# Reader_Schematic.net
KiCad netlist of a schematic drawn in Altium Designer
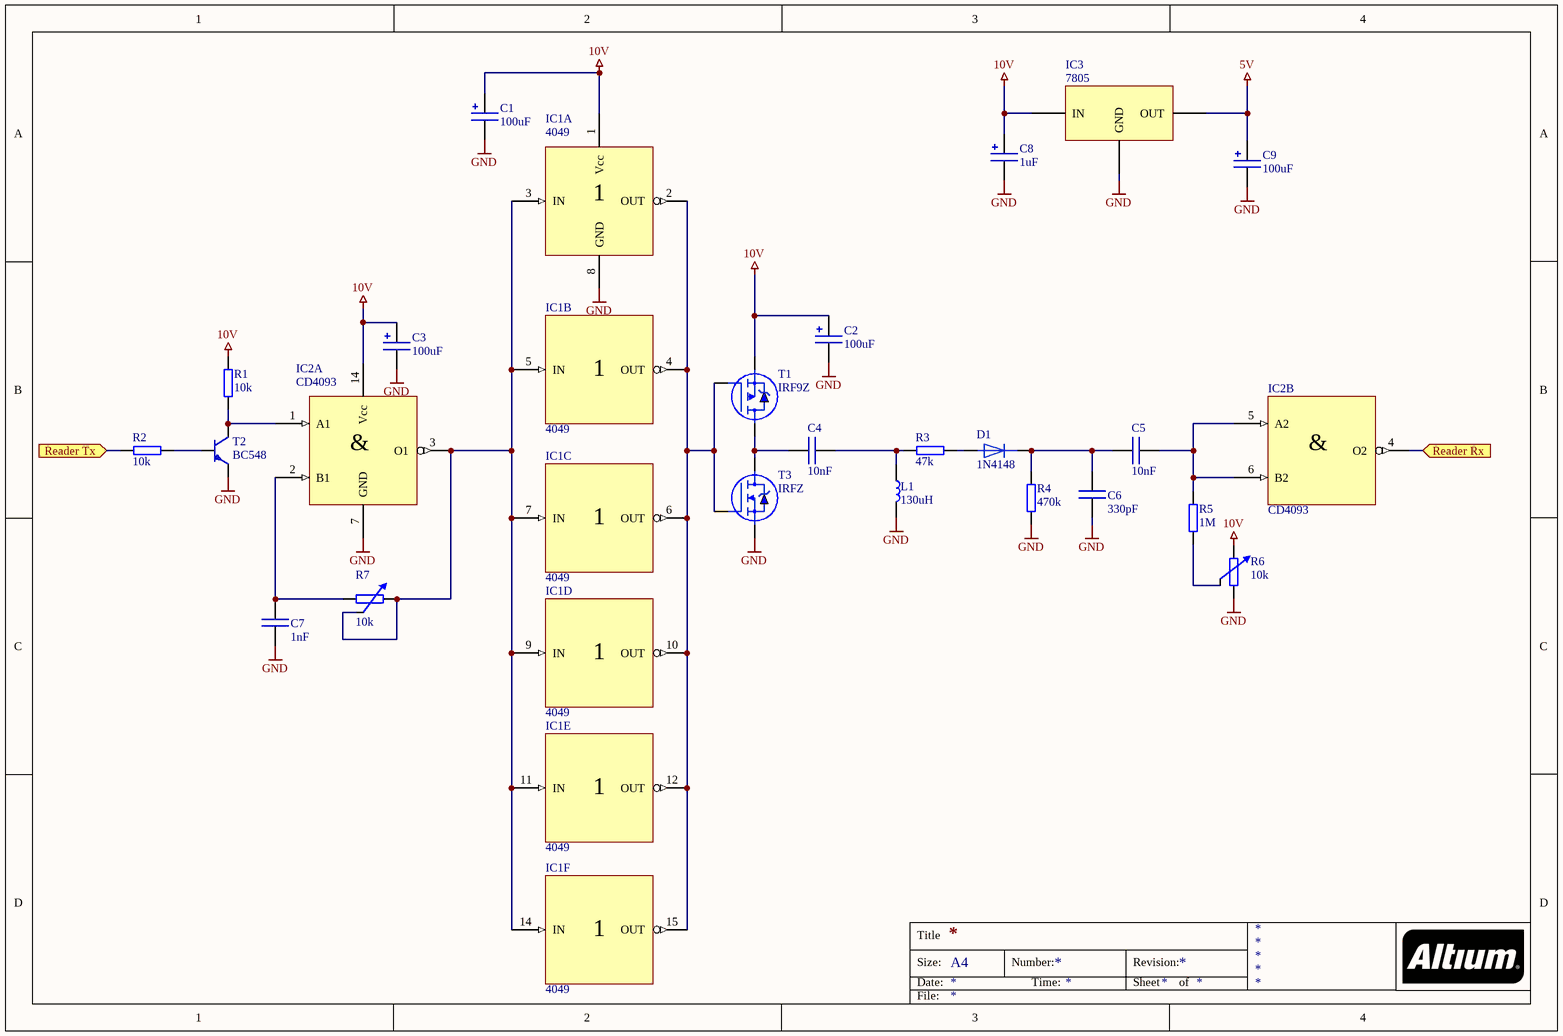
[diagram p0: Reader_Schematic.SchDoc]

(export (version "E")
  (design (tool "Eeschema 10.0.6"))
  (components
    (comp (ref "C1") (value "100uF") (footprint "ELKO_10_5.0") (libsource (lib "Staudi_Lib") (part "Elko")))
    (comp (ref "C2") (value "100uF") (footprint "ELKO_10_5.0") (libsource (lib "Staudi_Lib") (part "Elko")))
    (comp (ref "C3") (value "100uF") (footprint "ELKO_10_5.0") (libsource (lib "Staudi_Lib") (part "Elko")))
    (comp (ref "C4") (value "10nF") (footprint "0805") (libsource (lib "Staudi_Lib") (part "Cap")))
    (comp (ref "C5") (value "10nF") (footprint "0805") (libsource (lib "Staudi_Lib") (part "Cap")))
    (comp (ref "C6") (value "330pF") (footprint "0805") (libsource (lib "Staudi_Lib") (part "Cap")))
    (comp (ref "C7") (value "1nF") (footprint "0805") (libsource (lib "Staudi_Lib") (part "Cap")))
    (comp (ref "C8") (value "1uF") (footprint "ELKO_10_5.0") (libsource (lib "Staudi_Lib") (part "Elko")))
    (comp (ref "C9") (value "100uF") (footprint "ELKO_10_5.0") (libsource (lib "Staudi_Lib") (part "Elko")))
    (comp (ref "D1") (value "1N4148") (libsource (lib "Staudi_Lib") (part "Diode")))
    (comp (ref "IC1")
      (value "4049")
      (description "Hex Inverter")
      (libsource (lib "Staudi_Lib") (part "4049"))
    )
    (comp (ref "IC2")
      (value "CD4093")
      (description "Quad NAND with Schmitt Output")
      (libsource (lib "Staudi_Lib") (part "4093"))
    )
    (comp (ref "IC3")
      (value "7805")
      (description "5V Voltage regulator")
      (libsource (lib "Staudi_Lib") (part "7805"))
    )
    (comp (ref "L1")
      (value "130uH")
      (description "Inductor")
      (libsource (lib "Staudi_Lib") (part "Inductor"))
    )
    (comp (ref "R1") (value "10k") (footprint "Axial-04") (libsource (lib "Staudi_Lib") (part "Res")))
    (comp (ref "R2") (value "10k") (footprint "Axial-04") (libsource (lib "Staudi_Lib") (part "Res")))
    (comp (ref "R3") (value "47k") (footprint "Axial-04") (libsource (lib "Staudi_Lib") (part "Res")))
    (comp (ref "R4") (value "470k") (footprint "Axial-04") (libsource (lib "Staudi_Lib") (part "Res")))
    (comp (ref "R5") (value "1M") (footprint "Axial-04") (libsource (lib "Staudi_Lib") (part "Res")))
    (comp (ref "R6") (value "10k") (libsource (lib "Staudi_Lib") (part "Potentiometer")))
    (comp (ref "R7") (value "10k") (libsource (lib "Staudi_Lib") (part "Potentiometer")))
    (comp (ref "T1")
      (value "IRF9Z")
      (footprint "NDS0610")
      (libsource (lib "Staudi_Lib") (part "MOSFET P-Channel"))
    )
    (comp (ref "T2") (value "BC548") (footprint "2SC3324") (libsource (lib "Staudi_Lib") (part "NPN")))
    (comp (ref "T3")
      (value "IRFZ")
      (footprint "SOT-23")
      (libsource (lib "Staudi_Lib") (part "MOSFET N-Channel"))
    )
  )
  (nets
    (net (code "1") (name "/Reader Rx") (class "Default")
      (node (ref "IC2") (pin "4") (pinfunction "O2_4") (pintype "output"))
    )
    (net (code "2") (name "/Reader Tx") (class "Default")
      (node (ref "R2") (pin "1") (pinfunction "1_1") (pintype "passive"))
    )
    (net (code "3") (name "5V") (class "Default")
      (node (ref "C9") (pin "1") (pinfunction "1_1") (pintype "passive"))
      (node (ref "IC3") (pin "2") (pinfunction "OUT_2") (pintype "passive"))
    )
    (net (code "4") (name "10V") (class "Default")
      (node (ref "C1") (pin "1") (pinfunction "1_1") (pintype "passive"))
      (node (ref "C2") (pin "1") (pinfunction "1_1") (pintype "passive"))
      (node (ref "C3") (pin "1") (pinfunction "1_1") (pintype "passive"))
      (node (ref "C8") (pin "1") (pinfunction "1_1") (pintype "passive"))
      (node (ref "IC1") (pin "1") (pinfunction "Vcc_1") (pintype "passive"))
      (node (ref "IC2") (pin "14") (pinfunction "Vcc_14") (pintype "passive"))
      (node (ref "IC3") (pin "1") (pinfunction "IN_1") (pintype "passive"))
      (node (ref "R1") (pin "2") (pinfunction "2_2") (pintype "passive"))
      (node (ref "R6") (pin "2") (pinfunction "2_2") (pintype "passive"))
      (node (ref "T1") (pin "2") (pinfunction "Source_2") (pintype "passive"))
    )
    (net (code "5") (name "GND") (class "Default")
      (node (ref "C1") (pin "2") (pinfunction "2_2") (pintype "passive"))
      (node (ref "C2") (pin "2") (pinfunction "2_2") (pintype "passive"))
      (node (ref "C3") (pin "2") (pinfunction "2_2") (pintype "passive"))
      (node (ref "C6") (pin "1") (pinfunction "1_1") (pintype "passive"))
      (node (ref "C7") (pin "1") (pinfunction "1_1") (pintype "passive"))
      (node (ref "C8") (pin "2") (pinfunction "2_2") (pintype "passive"))
      (node (ref "C9") (pin "2") (pinfunction "2_2") (pintype "passive"))
      (node (ref "IC1") (pin "8") (pinfunction "GND_8") (pintype "passive"))
      (node (ref "IC2") (pin "7") (pinfunction "GND_7") (pintype "passive"))
      (node (ref "IC3") (pin "3") (pinfunction "GND_3") (pintype "passive"))
      (node (ref "L1") (pin "1") (pinfunction "1_1") (pintype "passive"))
      (node (ref "R4") (pin "1") (pinfunction "1_1") (pintype "passive"))
      (node (ref "R6") (pin "1") (pinfunction "1_1") (pintype "passive"))
      (node (ref "T2") (pin "2") (pinfunction "Emitter_2") (pintype "passive"))
      (node (ref "T3") (pin "3") (pinfunction "Source_3") (pintype "passive"))
    )
    (net (code "6") (name "Net-(C4-Pad2)") (class "Default")
      (node (ref "C4") (pin "2") (pinfunction "2_2") (pintype "passive"))
      (node (ref "L1") (pin "2") (pinfunction "2_2") (pintype "passive"))
      (node (ref "R3") (pin "1") (pinfunction "1_1") (pintype "passive"))
    )
    (net (code "7") (name "Net-(D1-Anode)") (class "Default")
      (node (ref "D1") (pin "1") (pinfunction "Anode_1") (pintype "passive"))
      (node (ref "R3") (pin "2") (pinfunction "2_2") (pintype "passive"))
    )
    (net (code "8") (name "Net-(D1-Kathode)") (class "Default")
      (node (ref "C5") (pin "1") (pinfunction "1_1") (pintype "passive"))
      (node (ref "C6") (pin "2") (pinfunction "2_2") (pintype "passive"))
      (node (ref "D1") (pin "2") (pinfunction "Kathode_2") (pintype "passive"))
      (node (ref "R4") (pin "2") (pinfunction "2_2") (pintype "passive"))
    )
    (net (code "9") (name "Net-(IC1A-IN)") (class "Default")
      (node (ref "IC1") (pin "11") (pinfunction "IN_11") (pintype "input"))
      (node (ref "IC1") (pin "14") (pinfunction "IN_14") (pintype "input"))
      (node (ref "IC1") (pin "3") (pinfunction "IN_3") (pintype "input"))
      (node (ref "IC1") (pin "5") (pinfunction "IN_5") (pintype "input"))
      (node (ref "IC1") (pin "7") (pinfunction "IN_7") (pintype "input"))
      (node (ref "IC1") (pin "9") (pinfunction "IN_9") (pintype "input"))
      (node (ref "IC2") (pin "3") (pinfunction "O1_3") (pintype "output"))
      (node (ref "R7") (pin "2") (pinfunction "2_2") (pintype "passive"))
      (node (ref "R7") (pin "3") (pinfunction "3_3") (pintype "passive"))
    )
    (net (code "10") (name "Net-(IC1A-OUT)") (class "Default")
      (node (ref "IC1") (pin "10") (pinfunction "OUT_10") (pintype "output"))
      (node (ref "IC1") (pin "12") (pinfunction "OUT_12") (pintype "output"))
      (node (ref "IC1") (pin "15") (pinfunction "OUT_15") (pintype "output"))
      (node (ref "IC1") (pin "2") (pinfunction "OUT_2") (pintype "output"))
      (node (ref "IC1") (pin "4") (pinfunction "OUT_4") (pintype "output"))
      (node (ref "IC1") (pin "6") (pinfunction "OUT_6") (pintype "output"))
      (node (ref "T1") (pin "1") (pinfunction "Gate_1") (pintype "passive"))
      (node (ref "T3") (pin "1") (pinfunction "Gate_1") (pintype "passive"))
    )
    (net (code "11") (name "Net-(IC2A-A1)") (class "Default")
      (node (ref "IC2") (pin "1") (pinfunction "A1_1") (pintype "input"))
      (node (ref "R1") (pin "1") (pinfunction "1_1") (pintype "passive"))
      (node (ref "T2") (pin "3") (pinfunction "Collector_3") (pintype "passive"))
    )
    (net (code "12") (name "Net-(IC2A-B1)") (class "Default")
      (node (ref "C7") (pin "2") (pinfunction "2_2") (pintype "passive"))
      (node (ref "IC2") (pin "2") (pinfunction "B1_2") (pintype "input"))
      (node (ref "R7") (pin "1") (pinfunction "1_1") (pintype "passive"))
    )
    (net (code "13") (name "Net-(IC2B-A2)") (class "Default")
      (node (ref "C5") (pin "2") (pinfunction "2_2") (pintype "passive"))
      (node (ref "IC2") (pin "5") (pinfunction "A2_5") (pintype "input"))
      (node (ref "IC2") (pin "6") (pinfunction "B2_6") (pintype "input"))
      (node (ref "R5") (pin "2") (pinfunction "2_2") (pintype "passive"))
    )
    (net (code "14") (name "Net-(R5-Pad1)") (class "Default")
      (node (ref "R5") (pin "1") (pinfunction "1_1") (pintype "passive"))
      (node (ref "R6") (pin "3") (pinfunction "3_3") (pintype "passive"))
    )
    (net (code "15") (name "Net-(T1-Drain)") (class "Default")
      (node (ref "C4") (pin "1") (pinfunction "1_1") (pintype "passive"))
      (node (ref "T1") (pin "3") (pinfunction "Drain_3") (pintype "passive"))
      (node (ref "T3") (pin "2") (pinfunction "Drain_2") (pintype "passive"))
    )
    (net (code "16") (name "Net-(T2-Base)") (class "Default")
      (node (ref "R2") (pin "2") (pinfunction "2_2") (pintype "passive"))
      (node (ref "T2") (pin "1") (pinfunction "Base_1") (pintype "passive"))
    )
  )
)
